# 01072016wearable_v1_2_-_OK.net
KiCad netlist of a schematic drawn in EAGLE
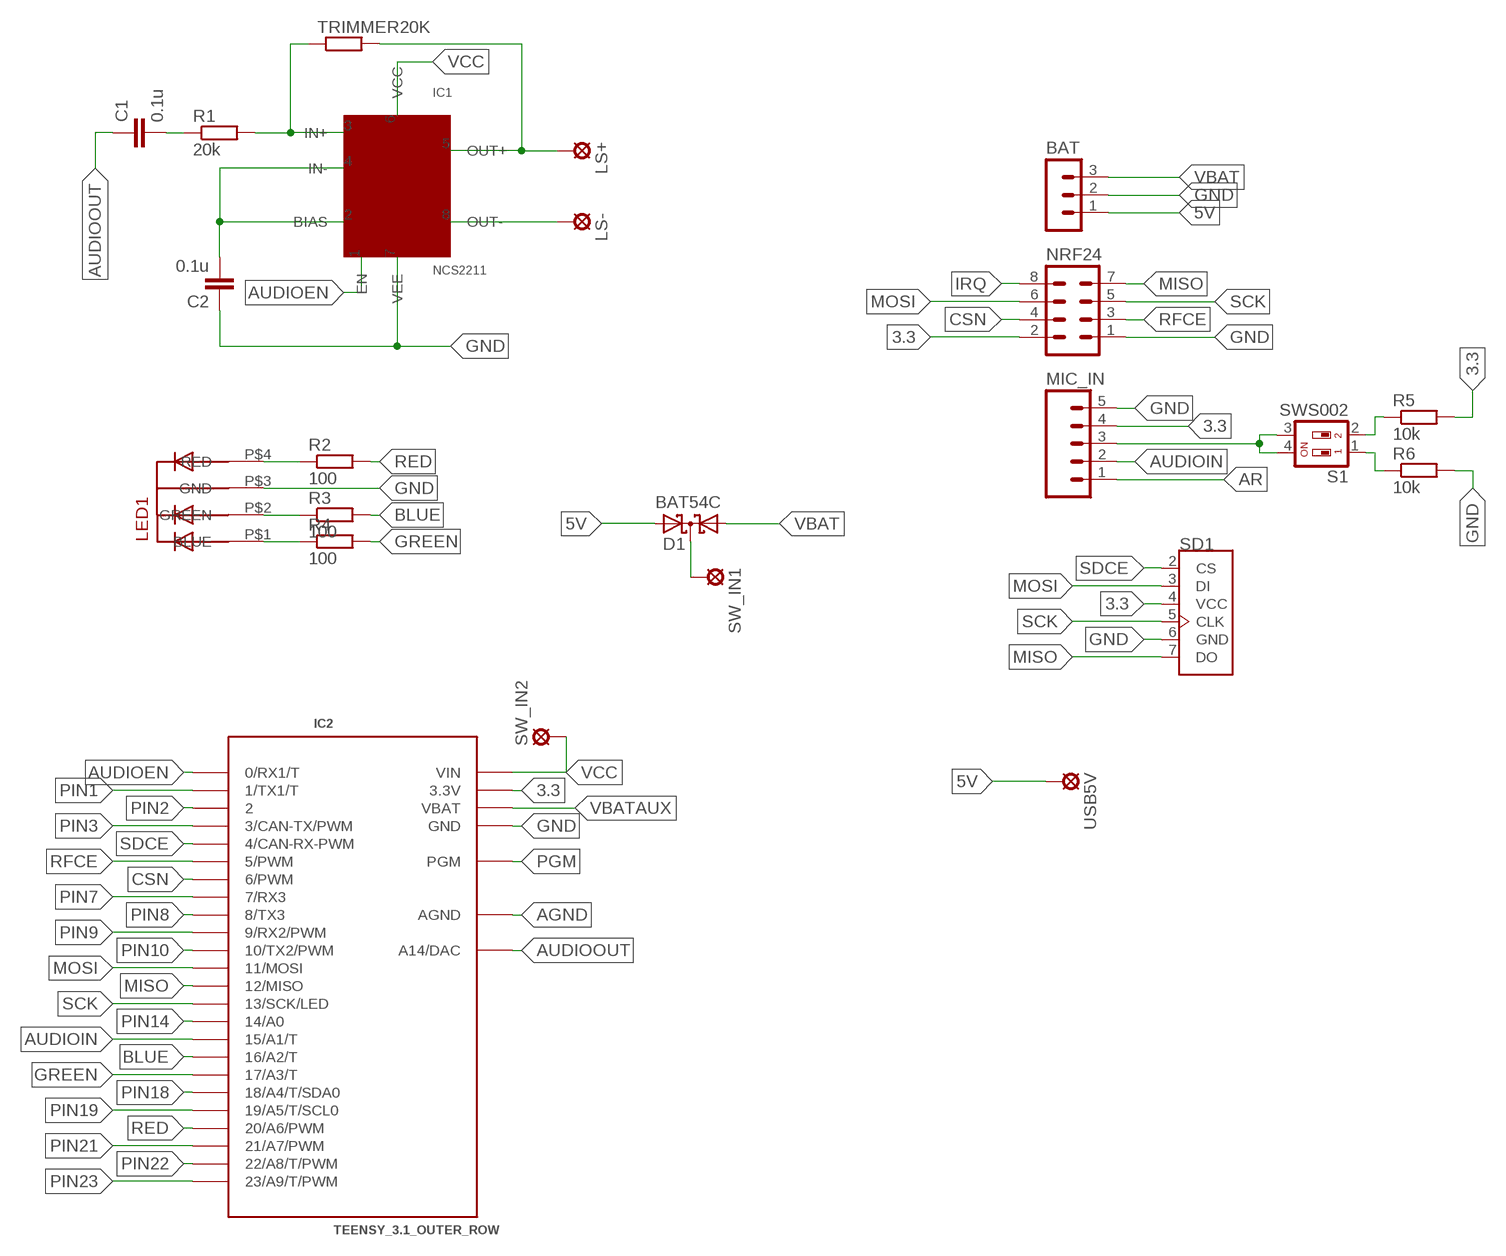
[diagram p0: schematic, sheet 1]

(export (version "E")
  (design (tool "Eeschema 10.0.6"))
  (components
    (comp (ref "BAT")
      (value "MA03-1")
      (footprint "eagle-import:MA03-1")
      (libsource (lib "eagle-import") (part "MA03-1"))
    )
    (comp (ref "C1")
      (value "0.1u")
      (footprint "eagle-import:C2.5-2")
      (libsource (lib "eagle-import") (part "C2.5/2"))
    )
    (comp (ref "C2")
      (value "0.1u")
      (footprint "eagle-import:C2.5-2")
      (libsource (lib "eagle-import") (part "C2.5/2"))
    )
    (comp (ref "D1")
      (value "BAT54C")
      (footprint "eagle-import:SOT23")
      (libsource (lib "eagle-import") (part "BAT54C"))
    )
    (comp (ref "IC1")
      (value "NCS2211")
      (footprint "eagle-import:SOIC-8")
      (libsource (lib "eagle-import") (part "NCS2211"))
    )
    (comp (ref "IC2")
      (value "TEENSY_3.1_OUTER_ROW")
      (footprint "eagle-import:TEENSY3-OUTER_ROW")
      (libsource (lib "eagle-import") (part "TEENSY_3.1_OUTER_ROW"))
    )
    (comp (ref "LED1")
      (value "5MMRGBLED")
      (footprint "eagle-import:LED5MMRGB")
      (libsource (lib "eagle-import") (part "5MMRGBLED"))
    )
    (comp (ref "LS+")
      (value "LSP10")
      (footprint "eagle-import:LSP10")
      (libsource (lib "eagle-import") (part "LSP10"))
    )
    (comp (ref "LS-")
      (value "LSP10")
      (footprint "eagle-import:LSP10")
      (libsource (lib "eagle-import") (part "LSP10"))
    )
    (comp (ref "MIC_IN")
      (value "MA05")
      (footprint "eagle-import:05PA")
      (libsource (lib "eagle-import") (part "MA05"))
    )
    (comp (ref "NRF24")
      (value "MA04-2")
      (footprint "eagle-import:MA04-2")
      (libsource (lib "eagle-import") (part "MA04-2"))
    )
    (comp (ref "R1")
      (value "20k")
      (footprint "eagle-import:0204_7")
      (libsource (lib "eagle-import") (part "R-EU_0204/7"))
    )
    (comp (ref "R2")
      (value "100")
      (footprint "eagle-import:0207_2V")
      (libsource (lib "eagle-import") (part "R-EU_0207/2V"))
    )
    (comp (ref "R3")
      (value "100")
      (footprint "eagle-import:0207_2V")
      (libsource (lib "eagle-import") (part "R-EU_0207/2V"))
    )
    (comp (ref "R4")
      (value "100")
      (footprint "eagle-import:0207_2V")
      (libsource (lib "eagle-import") (part "R-EU_0207/2V"))
    )
    (comp (ref "R5")
      (value "10k")
      (footprint "eagle-import:0207_2V")
      (libsource (lib "eagle-import") (part "R-EU_0207/2V"))
    )
    (comp (ref "R6")
      (value "10k")
      (footprint "eagle-import:0207_2V")
      (libsource (lib "eagle-import") (part "R-EU_0207/2V"))
    )
    (comp (ref "S1")
      (value "SWS002")
      (footprint "eagle-import:SMS-002")
      (libsource (lib "eagle-import") (part "SWS002"))
    )
    (comp (ref "SD1")
      (value "MICROSD_SF-MICROSD")
      (footprint "eagle-import:MICROSD_MICROSD")
      (libsource (lib "eagle-import") (part "MICROSD_SF-MICROSD"))
    )
    (comp (ref "SW_IN1")
      (value "SE11")
      (footprint "eagle-import:SE11")
      (libsource (lib "eagle-import") (part "SE11"))
    )
    (comp (ref "SW_IN2")
      (value "SE11")
      (footprint "eagle-import:SE11")
      (libsource (lib "eagle-import") (part "SE11"))
    )
    (comp (ref "TRIMMER20K")
      (value "R-EU_0207/2V")
      (footprint "eagle-import:0207_2V")
      (libsource (lib "eagle-import") (part "R-EU_0207/2V"))
    )
    (comp (ref "USB5V")
      (value "LSP10")
      (footprint "eagle-import:LSP10")
      (libsource (lib "eagle-import") (part "LSP10"))
    )
  )
  (nets
    (net (code "1") (name "3.3") (class "Default")
      (node (ref "IC2") (pin "3.3V") (pinfunction "3.3V_3.3V") (pintype "power_in"))
      (node (ref "IC2") (pin "3.3V1") (pinfunction "3.3V_3.3V1") (pintype "power_in"))
      (node (ref "MIC_IN") (pin "4") (pinfunction "4_4") (pintype "passive"))
      (node (ref "NRF24") (pin "2") (pinfunction "2_2") (pintype "passive"))
      (node (ref "R5") (pin "2") (pinfunction "2_2") (pintype "passive"))
      (node (ref "SD1") (pin "4") (pinfunction "VCC_4") (pintype "power_in"))
    )
    (net (code "2") (name "5V") (class "Default")
      (node (ref "BAT") (pin "1") (pinfunction "1_1") (pintype "passive"))
      (node (ref "D1") (pin "2") (pinfunction "A2_2") (pintype "passive"))
      (node (ref "USB5V") (pin "MP") (pinfunction "MP_MP") (pintype "passive"))
    )
    (net (code "3") (name "AGND") (class "Default")
      (node (ref "IC2") (pin "AGND") (pinfunction "AGND_AGND") (pintype "power_in"))
    )
    (net (code "4") (name "AR") (class "Default")
      (node (ref "MIC_IN") (pin "1") (pinfunction "1_1") (pintype "passive"))
    )
    (net (code "5") (name "AUDIOEN") (class "Default")
      (node (ref "IC1") (pin "1") (pinfunction "EN_1") (pintype "bidirectional"))
      (node (ref "IC2") (pin "0") (pinfunction "0/RX1/T_0") (pintype "bidirectional"))
    )
    (net (code "6") (name "AUDIOIN") (class "Default")
      (node (ref "IC2") (pin "15/A1") (pinfunction "15/A1/T_15/A1") (pintype "bidirectional"))
      (node (ref "MIC_IN") (pin "2") (pinfunction "2_2") (pintype "passive"))
    )
    (net (code "7") (name "AUDIOOUT") (class "Default")
      (node (ref "C1") (pin "1") (pinfunction "1_1") (pintype "passive"))
      (node (ref "IC2") (pin "RESET/DAC") (pinfunction "A14/DAC_RESET/DAC") (pintype "bidirectional"))
    )
    (net (code "8") (name "BLUE") (class "Default")
      (node (ref "IC2") (pin "16/A2") (pinfunction "16/A2/T_16/A2") (pintype "bidirectional"))
      (node (ref "R3") (pin "2") (pinfunction "2_2") (pintype "passive"))
    )
    (net (code "9") (name "CSN") (class "Default")
      (node (ref "IC2") (pin "6") (pinfunction "6/PWM_6") (pintype "bidirectional"))
      (node (ref "NRF24") (pin "4") (pinfunction "4_4") (pintype "passive"))
    )
    (net (code "10") (name "GND") (class "Default")
      (node (ref "BAT") (pin "2") (pinfunction "2_2") (pintype "passive"))
      (node (ref "C2") (pin "1") (pinfunction "1_1") (pintype "passive"))
      (node (ref "IC1") (pin "7") (pinfunction "VEE_7") (pintype "bidirectional"))
      (node (ref "IC2") (pin "GND") (pinfunction "GND_GND") (pintype "power_in"))
      (node (ref "IC2") (pin "GND1") (pinfunction "GND_GND1") (pintype "power_in"))
      (node (ref "LED1") (pin "P$3") (pinfunction "GND_P$3") (pintype "bidirectional"))
      (node (ref "MIC_IN") (pin "5") (pinfunction "5_5") (pintype "passive"))
      (node (ref "NRF24") (pin "1") (pinfunction "1_1") (pintype "passive"))
      (node (ref "R6") (pin "2") (pinfunction "2_2") (pintype "passive"))
      (node (ref "SD1") (pin "6") (pinfunction "GND_6") (pintype "power_in"))
    )
    (net (code "11") (name "GREEN") (class "Default")
      (node (ref "IC2") (pin "17/A3") (pinfunction "17/A3/T_17/A3") (pintype "bidirectional"))
      (node (ref "R4") (pin "2") (pinfunction "2_2") (pintype "passive"))
    )
    (net (code "12") (name "IRQ") (class "Default")
      (node (ref "NRF24") (pin "8") (pinfunction "8_8") (pintype "passive"))
    )
    (net (code "13") (name "MISO") (class "Default")
      (node (ref "IC2") (pin "12") (pinfunction "12/MISO_12") (pintype "bidirectional"))
      (node (ref "NRF24") (pin "7") (pinfunction "7_7") (pintype "passive"))
      (node (ref "SD1") (pin "7") (pinfunction "DO_7") (pintype "output"))
    )
    (net (code "14") (name "MOSI") (class "Default")
      (node (ref "IC2") (pin "11") (pinfunction "11/MOSI_11") (pintype "bidirectional"))
      (node (ref "NRF24") (pin "6") (pinfunction "6_6") (pintype "passive"))
      (node (ref "SD1") (pin "3") (pinfunction "DI_3") (pintype "input"))
    )
    (net (code "15") (name "Net-(C1-Pad2)") (class "Default")
      (node (ref "C1") (pin "2") (pinfunction "2_2") (pintype "passive"))
      (node (ref "R1") (pin "1") (pinfunction "1_1") (pintype "passive"))
    )
    (net (code "16") (name "Net-(D1-CC)") (class "Default")
      (node (ref "D1") (pin "3") (pinfunction "CC_3") (pintype "passive"))
      (node (ref "SW_IN1") (pin "MP") (pinfunction "MP_MP") (pintype "passive"))
    )
    (net (code "17") (name "Net-(IC1-BIAS)") (class "Default")
      (node (ref "C2") (pin "2") (pinfunction "2_2") (pintype "passive"))
      (node (ref "IC1") (pin "2") (pinfunction "BIAS_2") (pintype "bidirectional"))
      (node (ref "IC1") (pin "4") (pinfunction "IN-_4") (pintype "bidirectional"))
    )
    (net (code "18") (name "Net-(IC1-IN+)") (class "Default")
      (node (ref "IC1") (pin "3") (pinfunction "IN+_3") (pintype "bidirectional"))
      (node (ref "R1") (pin "2") (pinfunction "2_2") (pintype "passive"))
      (node (ref "TRIMMER20K") (pin "1") (pinfunction "1_1") (pintype "passive"))
    )
    (net (code "19") (name "Net-(IC1-OUT+)") (class "Default")
      (node (ref "IC1") (pin "5") (pinfunction "OUT+_5") (pintype "bidirectional"))
      (node (ref "LS+") (pin "MP") (pinfunction "MP_MP") (pintype "passive"))
      (node (ref "TRIMMER20K") (pin "2") (pinfunction "2_2") (pintype "passive"))
    )
    (net (code "20") (name "Net-(IC1-OUT-)") (class "Default")
      (node (ref "IC1") (pin "8") (pinfunction "OUT-_8") (pintype "bidirectional"))
      (node (ref "LS-") (pin "MP") (pinfunction "MP_MP") (pintype "passive"))
    )
    (net (code "21") (name "Net-(LED1-BLUE)") (class "Default")
      (node (ref "LED1") (pin "P$1") (pinfunction "BLUE_P$1") (pintype "bidirectional"))
      (node (ref "R4") (pin "1") (pinfunction "1_1") (pintype "passive"))
    )
    (net (code "22") (name "Net-(LED1-GREEN)") (class "Default")
      (node (ref "LED1") (pin "P$2") (pinfunction "GREEN_P$2") (pintype "bidirectional"))
      (node (ref "R3") (pin "1") (pinfunction "1_1") (pintype "passive"))
    )
    (net (code "23") (name "Net-(LED1-RED)") (class "Default")
      (node (ref "LED1") (pin "P$4") (pinfunction "RED_P$4") (pintype "bidirectional"))
      (node (ref "R2") (pin "1") (pinfunction "1_1") (pintype "passive"))
    )
    (net (code "24") (name "Net-(MIC_IN-Pad3)") (class "Default")
      (node (ref "MIC_IN") (pin "3") (pinfunction "3_3") (pintype "passive"))
      (node (ref "S1") (pin "3") (pinfunction "3_3") (pintype "passive"))
      (node (ref "S1") (pin "4") (pinfunction "4_4") (pintype "passive"))
    )
    (net (code "25") (name "Net-(R5-Pad1)") (class "Default")
      (node (ref "R5") (pin "1") (pinfunction "1_1") (pintype "passive"))
      (node (ref "S1") (pin "2") (pinfunction "2_2") (pintype "passive"))
    )
    (net (code "26") (name "Net-(R6-Pad1)") (class "Default")
      (node (ref "R6") (pin "1") (pinfunction "1_1") (pintype "passive"))
      (node (ref "S1") (pin "1") (pinfunction "1_1") (pintype "passive"))
    )
    (net (code "27") (name "PGM") (class "Default")
      (node (ref "IC2") (pin "PGM") (pinfunction "PGM_PGM") (pintype "bidirectional"))
    )
    (net (code "28") (name "PIN1") (class "Default")
      (node (ref "IC2") (pin "1") (pinfunction "1/TX1/T_1") (pintype "bidirectional"))
    )
    (net (code "29") (name "PIN2") (class "Default")
      (node (ref "IC2") (pin "2") (pinfunction "2_2") (pintype "bidirectional"))
    )
    (net (code "30") (name "PIN3") (class "Default")
      (node (ref "IC2") (pin "3") (pinfunction "3/CAN-TX/PWM_3") (pintype "bidirectional"))
    )
    (net (code "31") (name "PIN7") (class "Default")
      (node (ref "IC2") (pin "7") (pinfunction "7/RX3_7") (pintype "bidirectional"))
    )
    (net (code "32") (name "PIN8") (class "Default")
      (node (ref "IC2") (pin "8") (pinfunction "8/TX3_8") (pintype "bidirectional"))
    )
    (net (code "33") (name "PIN9") (class "Default")
      (node (ref "IC2") (pin "9") (pinfunction "9/RX2/PWM_9") (pintype "bidirectional"))
    )
    (net (code "34") (name "PIN10") (class "Default")
      (node (ref "IC2") (pin "10") (pinfunction "10/TX2/PWM_10") (pintype "bidirectional"))
    )
    (net (code "35") (name "PIN14") (class "Default")
      (node (ref "IC2") (pin "14/A0") (pinfunction "14/A0_14/A0") (pintype "bidirectional"))
    )
    (net (code "36") (name "PIN18") (class "Default")
      (node (ref "IC2") (pin "18/A4") (pinfunction "18/A4/T/SDA0_18/A4") (pintype "bidirectional"))
    )
    (net (code "37") (name "PIN19") (class "Default")
      (node (ref "IC2") (pin "19/A5") (pinfunction "19/A5/T/SCL0_19/A5") (pintype "bidirectional"))
    )
    (net (code "38") (name "PIN21") (class "Default")
      (node (ref "IC2") (pin "21/A7") (pinfunction "21/A7/PWM_21/A7") (pintype "bidirectional"))
    )
    (net (code "39") (name "PIN22") (class "Default")
      (node (ref "IC2") (pin "22/A8") (pinfunction "22/A8/T/PWM_22/A8") (pintype "bidirectional"))
    )
    (net (code "40") (name "PIN23") (class "Default")
      (node (ref "IC2") (pin "23/A9") (pinfunction "23/A9/T/PWM_23/A9") (pintype "bidirectional"))
    )
    (net (code "41") (name "RED") (class "Default")
      (node (ref "IC2") (pin "20/A6") (pinfunction "20/A6/PWM_20/A6") (pintype "bidirectional"))
      (node (ref "R2") (pin "2") (pinfunction "2_2") (pintype "passive"))
    )
    (net (code "42") (name "RFCE") (class "Default")
      (node (ref "IC2") (pin "5") (pinfunction "5/PWM_5") (pintype "bidirectional"))
      (node (ref "NRF24") (pin "3") (pinfunction "3_3") (pintype "passive"))
    )
    (net (code "43") (name "SCK") (class "Default")
      (node (ref "IC2") (pin "13") (pinfunction "13/SCK/LED_13") (pintype "bidirectional"))
      (node (ref "NRF24") (pin "5") (pinfunction "5_5") (pintype "passive"))
      (node (ref "SD1") (pin "5") (pinfunction "CLK_5") (pintype "input"))
    )
    (net (code "44") (name "SDCE") (class "Default")
      (node (ref "IC2") (pin "4") (pinfunction "4/CAN-RX-PWM_4") (pintype "bidirectional"))
      (node (ref "SD1") (pin "2") (pinfunction "CS_2") (pintype "input"))
    )
    (net (code "45") (name "VBAT") (class "Default")
      (node (ref "BAT") (pin "3") (pinfunction "3_3") (pintype "passive"))
      (node (ref "D1") (pin "1") (pinfunction "A1_1") (pintype "passive"))
    )
    (net (code "46") (name "VBATAUX") (class "Default")
      (node (ref "IC2") (pin "VBAT") (pinfunction "VBAT_VBAT") (pintype "power_in"))
    )
    (net (code "47") (name "VCC") (class "Default")
      (node (ref "IC1") (pin "6") (pinfunction "VCC_6") (pintype "bidirectional"))
      (node (ref "IC2") (pin "VIN") (pinfunction "VIN_VIN") (pintype "power_in"))
      (node (ref "SW_IN2") (pin "MP") (pinfunction "MP_MP") (pintype "passive"))
    )
  )
)
